# astable_555_timer.net
KiCad netlist of a schematic drawn in EAGLE
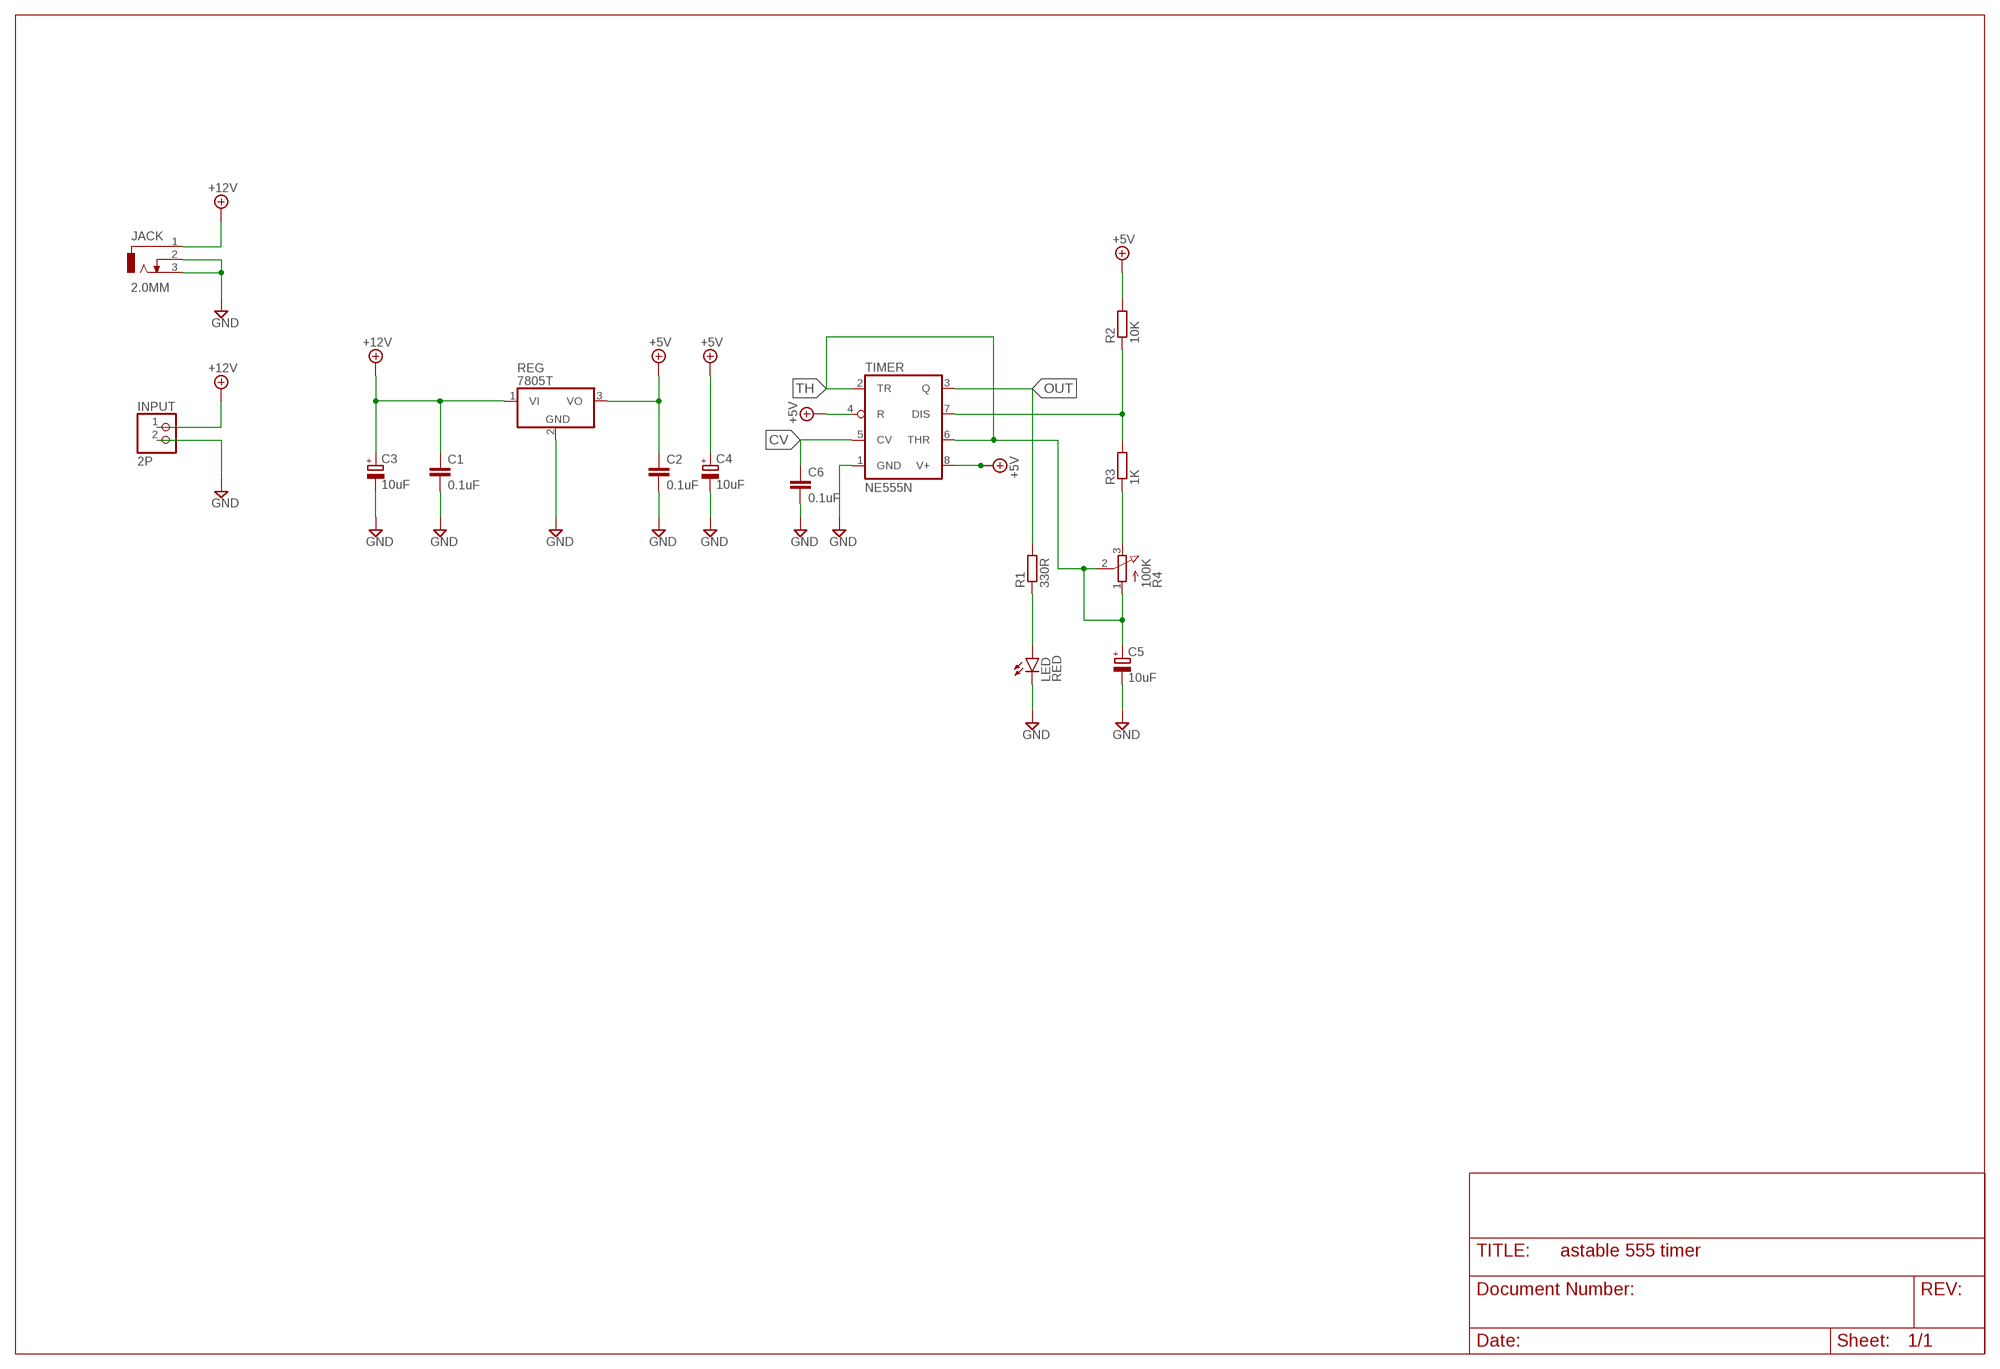
[diagram p0: schematic, sheet 1]

(export (version "E")
  (design (tool "Eeschema 10.0.6"))
  (components
    (comp (ref "C1")
      (value "0.1uF")
      (footprint "eagle-import:C050-030X075")
      (libsource (lib "eagle-import") (part "C-EU050-030X075"))
    )
    (comp (ref "C2")
      (value "0.1uF")
      (footprint "eagle-import:C050-030X075")
      (libsource (lib "eagle-import") (part "C-EU050-030X075"))
    )
    (comp (ref "C3")
      (value "10uF")
      (footprint "eagle-import:E3,5-8")
      (libsource (lib "eagle-import") (part "CPOL-EUE3.5-8"))
    )
    (comp (ref "C4")
      (value "10uF")
      (footprint "eagle-import:E3,5-8")
      (libsource (lib "eagle-import") (part "CPOL-EUE3.5-8"))
    )
    (comp (ref "C5")
      (value "10uF")
      (footprint "eagle-import:E3,5-8")
      (libsource (lib "eagle-import") (part "CPOL-EUE3.5-8"))
    )
    (comp (ref "C6")
      (value "0.1uF")
      (footprint "eagle-import:C050-030X075")
      (libsource (lib "eagle-import") (part "C-EU050-030X075"))
    )
    (comp (ref "INPUT")
      (value "2P")
      (footprint "eagle-import:1X02")
      (libsource (lib "eagle-import") (part "PINHD-1X2"))
    )
    (comp (ref "JACK")
      (value "2.0MM")
      (footprint "eagle-import:DCJ0202")
      (libsource (lib "eagle-import") (part "DCJ0202"))
    )
    (comp (ref "LED")
      (value "RED")
      (footprint "eagle-import:LED3MM")
      (libsource (lib "eagle-import") (part "LED3MM"))
    )
    (comp (ref "R1")
      (value "330R")
      (footprint "eagle-import:0207_10")
      (libsource (lib "eagle-import") (part "R-EU_0207/10"))
    )
    (comp (ref "R2")
      (value "10K")
      (footprint "eagle-import:0207_10")
      (libsource (lib "eagle-import") (part "R-EU_0207/10"))
    )
    (comp (ref "R3")
      (value "1K")
      (footprint "eagle-import:0207_10")
      (libsource (lib "eagle-import") (part "R-EU_0207/10"))
    )
    (comp (ref "R4")
      (value "100K")
      (footprint "eagle-import:3RP_1610N")
      (libsource (lib "eagle-import") (part "3RP/1610N"))
    )
    (comp (ref "REG")
      (value "7805T")
      (footprint "eagle-import:TO220H")
      (libsource (lib "eagle-import") (part "78T05"))
    )
    (comp (ref "TIMER")
      (value "NE555N")
      (footprint "eagle-import:DIL08")
      (libsource (lib "eagle-import") (part "555NNE"))
    )
  )
  (nets
    (net (code "1") (name "+5V") (class "Default")
      (node (ref "C2") (pin "1") (pinfunction "1_1") (pintype "passive"))
      (node (ref "C4") (pin "+") (pinfunction "+_+") (pintype "passive"))
      (node (ref "R2") (pin "2") (pinfunction "2_2") (pintype "passive"))
      (node (ref "REG") (pin "3") (pinfunction "VO_3") (pintype "passive"))
      (node (ref "TIMER") (pin "4") (pinfunction "R_4") (pintype "input"))
      (node (ref "TIMER") (pin "8") (pinfunction "V+_8") (pintype "power_in"))
    )
    (net (code "2") (name "+12V") (class "Default")
      (node (ref "C1") (pin "1") (pinfunction "1_1") (pintype "passive"))
      (node (ref "C3") (pin "+") (pinfunction "+_+") (pintype "passive"))
      (node (ref "INPUT") (pin "1") (pinfunction "1_1") (pintype "passive"))
      (node (ref "JACK") (pin "1") (pinfunction "1_1") (pintype "passive"))
      (node (ref "REG") (pin "1") (pinfunction "VI_1") (pintype "input"))
    )
    (net (code "3") (name "CV") (class "Default")
      (node (ref "C6") (pin "1") (pinfunction "1_1") (pintype "passive"))
      (node (ref "TIMER") (pin "5") (pinfunction "CV_5") (pintype "input"))
    )
    (net (code "4") (name "GND") (class "Default")
      (node (ref "C1") (pin "2") (pinfunction "2_2") (pintype "passive"))
      (node (ref "C2") (pin "2") (pinfunction "2_2") (pintype "passive"))
      (node (ref "C3") (pin "-") (pinfunction "-_-") (pintype "passive"))
      (node (ref "C4") (pin "-") (pinfunction "-_-") (pintype "passive"))
      (node (ref "C5") (pin "-") (pinfunction "-_-") (pintype "passive"))
      (node (ref "C6") (pin "2") (pinfunction "2_2") (pintype "passive"))
      (node (ref "INPUT") (pin "2") (pinfunction "2_2") (pintype "passive"))
      (node (ref "JACK") (pin "2") (pinfunction "2_2") (pintype "passive"))
      (node (ref "JACK") (pin "3") (pinfunction "3_3") (pintype "passive"))
      (node (ref "LED") (pin "K") (pinfunction "C_K") (pintype "passive"))
      (node (ref "REG") (pin "2") (pinfunction "GND_2") (pintype "passive"))
      (node (ref "TIMER") (pin "1") (pinfunction "GND_1") (pintype "power_in"))
    )
    (net (code "5") (name "Net-(LED-PadA)") (class "Default")
      (node (ref "LED") (pin "A") (pinfunction "A_A") (pintype "passive"))
      (node (ref "R1") (pin "1") (pinfunction "1_1") (pintype "passive"))
    )
    (net (code "6") (name "Net-(R4-E)") (class "Default")
      (node (ref "R3") (pin "1") (pinfunction "1_1") (pintype "passive"))
      (node (ref "R4") (pin "3") (pinfunction "E_3") (pintype "passive"))
    )
    (net (code "7") (name "Net-(TIMER-DIS)") (class "Default")
      (node (ref "R2") (pin "1") (pinfunction "1_1") (pintype "passive"))
      (node (ref "R3") (pin "2") (pinfunction "2_2") (pintype "passive"))
      (node (ref "TIMER") (pin "7") (pinfunction "DIS_7") (pintype "input"))
    )
    (net (code "8") (name "OUT") (class "Default")
      (node (ref "R1") (pin "2") (pinfunction "2_2") (pintype "passive"))
      (node (ref "TIMER") (pin "3") (pinfunction "Q_3") (pintype "output"))
    )
    (net (code "9") (name "TH") (class "Default")
      (node (ref "C5") (pin "+") (pinfunction "+_+") (pintype "passive"))
      (node (ref "R4") (pin "1") (pinfunction "A_1") (pintype "passive"))
      (node (ref "R4") (pin "2") (pinfunction "S_2") (pintype "passive"))
      (node (ref "TIMER") (pin "2") (pinfunction "TR_2") (pintype "input"))
      (node (ref "TIMER") (pin "6") (pinfunction "THR_6") (pintype "input"))
    )
  )
)
